# isoDebug-FTDI.net
KiCad netlist of a schematic drawn in Altium Designer
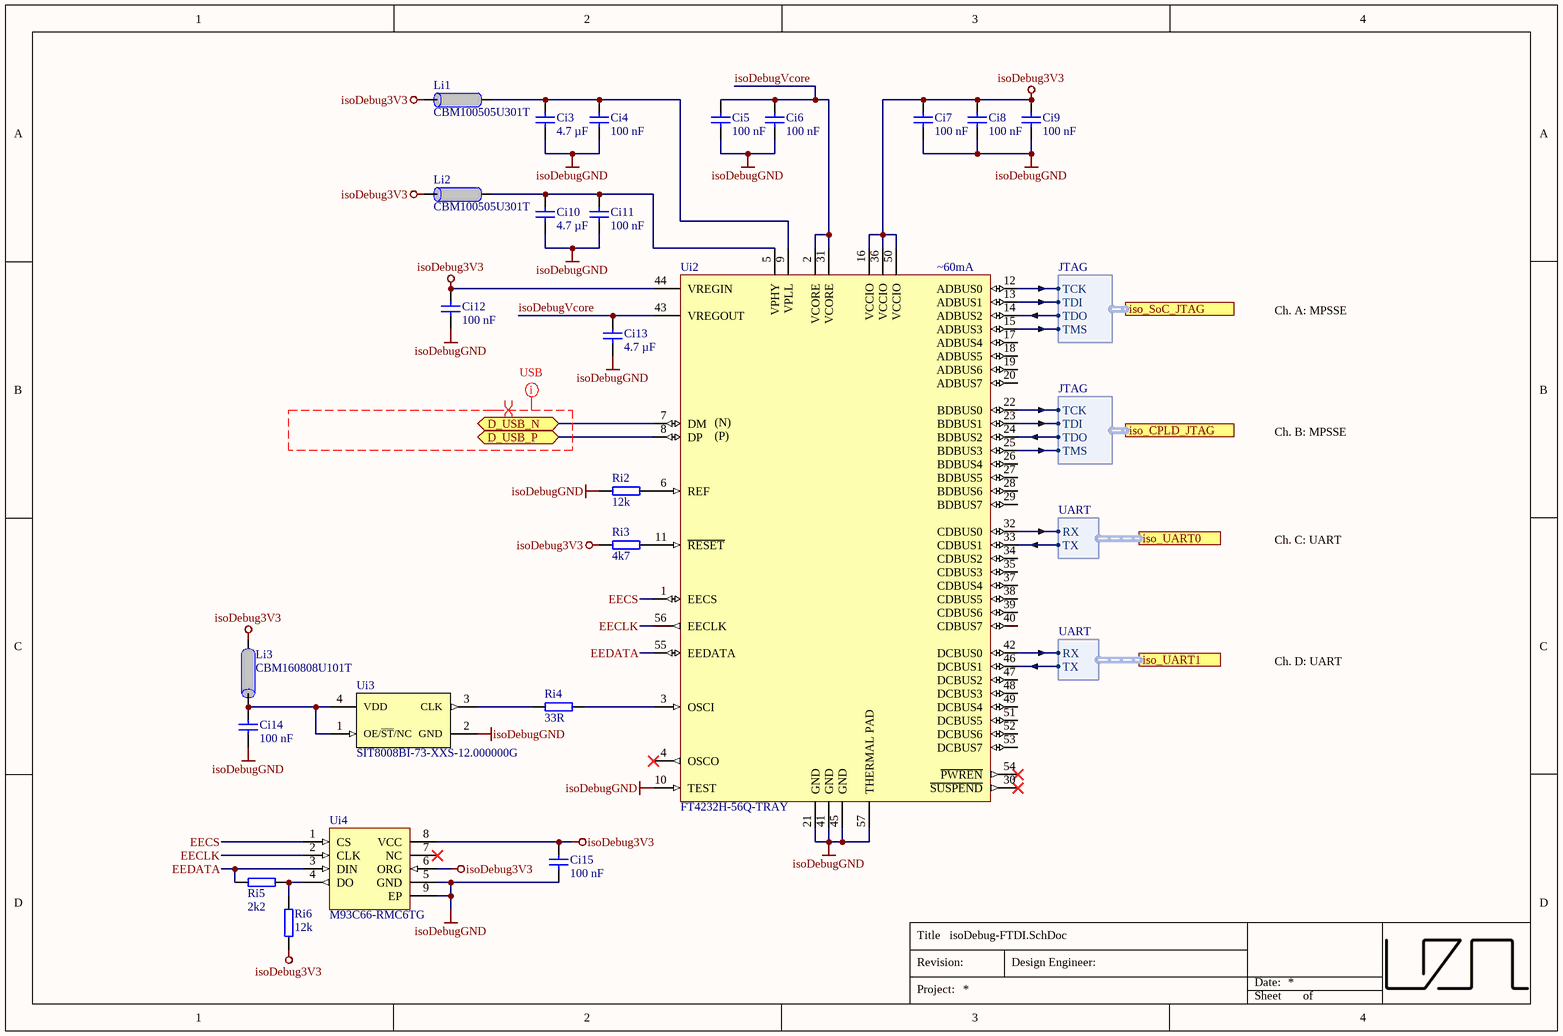
[diagram p0: isoDebug-FTDI.SchDoc]

(export (version "E")
  (design (tool "Eeschema 10.0.6"))
  (components
    (comp (ref "Ci3")
      (value "4.7 µF")
      (footprint "C_0603_TE")
      (description "Generic capacitor")
      (fields
        (field (name "MANUFACTURER PART NUMBER") "UZgen_C_0603_4.7uF_16V_X5R")
        (field (name "MANUFACTURER") "UZgen")
        (field (name "CREATED FROM") "MGeier")
      )
      (libsource (lib "user") (part "CAP-NP"))
    )
    (comp (ref "Ci4")
      (value "100 nF")
      (footprint "C_0402_TE")
      (description "Generic capacitor")
      (fields
        (field (name "MANUFACTURER PART NUMBER") "UZgen_C_0402_100nF_50V_X7R")
        (field (name "MANUFACTURER") "UZgen")
        (field (name "CREATED FROM") "UZgenTool")
      )
      (libsource (lib "user") (part "CAP-NP"))
    )
    (comp (ref "Ci5")
      (value "100 nF")
      (footprint "C_0402_TE")
      (description "Generic capacitor")
      (fields
        (field (name "MANUFACTURER PART NUMBER") "UZgen_C_0402_100nF_50V_X7R")
        (field (name "MANUFACTURER") "UZgen")
        (field (name "CREATED FROM") "UZgenTool")
      )
      (libsource (lib "user") (part "CAP-NP"))
    )
    (comp (ref "Ci6")
      (value "100 nF")
      (footprint "C_0402_TE")
      (description "Generic capacitor")
      (fields
        (field (name "MANUFACTURER PART NUMBER") "UZgen_C_0402_100nF_50V_X7R")
        (field (name "MANUFACTURER") "UZgen")
        (field (name "CREATED FROM") "UZgenTool")
      )
      (libsource (lib "user") (part "CAP-NP"))
    )
    (comp (ref "Ci7")
      (value "100 nF")
      (footprint "C_0402_TE")
      (description "Generic capacitor")
      (fields
        (field (name "MANUFACTURER PART NUMBER") "UZgen_C_0402_100nF_50V_X7R")
        (field (name "MANUFACTURER") "UZgen")
        (field (name "CREATED FROM") "UZgenTool")
      )
      (libsource (lib "user") (part "CAP-NP"))
    )
    (comp (ref "Ci8")
      (value "100 nF")
      (footprint "C_0402_TE")
      (description "Generic capacitor")
      (fields
        (field (name "MANUFACTURER PART NUMBER") "UZgen_C_0402_100nF_50V_X7R")
        (field (name "MANUFACTURER") "UZgen")
        (field (name "CREATED FROM") "UZgenTool")
      )
      (libsource (lib "user") (part "CAP-NP"))
    )
    (comp (ref "Ci9")
      (value "100 nF")
      (footprint "C_0402_TE")
      (description "Generic capacitor")
      (fields
        (field (name "MANUFACTURER PART NUMBER") "UZgen_C_0402_100nF_50V_X7R")
        (field (name "MANUFACTURER") "UZgen")
        (field (name "CREATED FROM") "UZgenTool")
      )
      (libsource (lib "user") (part "CAP-NP"))
    )
    (comp (ref "Ci10")
      (value "4.7 µF")
      (footprint "C_0603_TE")
      (description "Generic capacitor")
      (fields
        (field (name "MANUFACTURER PART NUMBER") "UZgen_C_0603_4.7uF_16V_X5R")
        (field (name "MANUFACTURER") "UZgen")
        (field (name "CREATED FROM") "MGeier")
      )
      (libsource (lib "user") (part "CAP-NP"))
    )
    (comp (ref "Ci11")
      (value "100 nF")
      (footprint "C_0402_TE")
      (description "Generic capacitor")
      (fields
        (field (name "MANUFACTURER PART NUMBER") "UZgen_C_0402_100nF_50V_X7R")
        (field (name "MANUFACTURER") "UZgen")
        (field (name "CREATED FROM") "UZgenTool")
      )
      (libsource (lib "user") (part "CAP-NP"))
    )
    (comp (ref "Ci12")
      (value "100 nF")
      (footprint "C_0402_TE")
      (description "Generic capacitor")
      (fields
        (field (name "MANUFACTURER PART NUMBER") "UZgen_C_0402_100nF_50V_X7R")
        (field (name "MANUFACTURER") "UZgen")
        (field (name "CREATED FROM") "UZgenTool")
      )
      (libsource (lib "user") (part "CAP-NP"))
    )
    (comp (ref "Ci13")
      (value "4.7 µF")
      (footprint "C_0603_TE")
      (description "Generic capacitor")
      (fields
        (field (name "MANUFACTURER PART NUMBER") "UZgen_C_0603_4.7uF_16V_X5R")
        (field (name "MANUFACTURER") "UZgen")
        (field (name "CREATED FROM") "MGeier")
      )
      (libsource (lib "user") (part "CAP-NP"))
    )
    (comp (ref "Ci14")
      (value "100 nF")
      (footprint "C_0402_TE")
      (description "Generic capacitor")
      (fields
        (field (name "MANUFACTURER PART NUMBER") "UZgen_C_0402_100nF_50V_X7R")
        (field (name "MANUFACTURER") "UZgen")
        (field (name "CREATED FROM") "UZgenTool")
      )
      (libsource (lib "user") (part "CAP-NP"))
    )
    (comp (ref "Ci15")
      (value "100 nF")
      (footprint "C_0402_TE")
      (description "Generic capacitor")
      (fields
        (field (name "MANUFACTURER PART NUMBER") "UZgen_C_0402_100nF_50V_X7R")
        (field (name "MANUFACTURER") "UZgen")
        (field (name "CREATED FROM") "UZgenTool")
      )
      (libsource (lib "user") (part "CAP-NP"))
    )
    (comp (ref "Li1")
      (value "CBM100505U301T")
      (footprint "IND_0402_TE")
      (description "300mΩ ±25% 300Ω@100MHz 0402 Ferrite Beads ROHS")
      (fields
        (field (name "MANUFACTURER") "FH (Guangdong Fenghua Advanced Tech)")
        (field (name "LCSC PART NUMBER") "C394406")
        (field (name "CREATED FROM") "AGeiger")
      )
      (libsource (lib "") (part "Ferrite_Bead_1"))
    )
    (comp (ref "Li2")
      (value "CBM100505U301T")
      (footprint "IND_0402_TE")
      (description "300mΩ ±25% 300Ω@100MHz 0402 Ferrite Beads ROHS")
      (fields
        (field (name "MANUFACTURER") "FH (Guangdong Fenghua Advanced Tech)")
        (field (name "LCSC PART NUMBER") "C394406")
        (field (name "CREATED FROM") "AGeiger")
      )
      (libsource (lib "") (part "Ferrite_Bead_1"))
    )
    (comp (ref "Li3")
      (value "CBM160808U101T")
      (footprint "IND_0603_TE")
      (description "60mΩ ±25% 100Ω@100MHz 0603 Ferrite Beads ROHS")
      (fields
        (field (name "MANUFACTURER") "FH (Guangdong Fenghua Advanced Tech)")
        (field (name "LCSC PART NUMBER") "C361675")
        (field (name "CREATED FROM") "AGeiger")
      )
      (libsource (lib "user") (part "Ferrite_Bead"))
    )
    (comp (ref "Ri2")
      (value "12k")
      (footprint "R_0603_TE")
      (description "Generic resistor")
      (fields
        (field (name "MANUFACTURER PART NUMBER") "UZgen_R_0603_12k")
        (field (name "MANUFACTURER") "UZgen")
        (field (name "CREATED FROM") "UZgenTool")
      )
      (libsource (lib "user") (part "RES"))
    )
    (comp (ref "Ri3")
      (value "4k7")
      (footprint "R_0603_TE")
      (description "Generic resistor")
      (fields
        (field (name "MANUFACTURER PART NUMBER") "UZgen_R_0603_4k7")
        (field (name "MANUFACTURER") "UZgen")
        (field (name "CREATED FROM") "UZgenTool")
      )
      (libsource (lib "user") (part "RES"))
    )
    (comp (ref "Ri4")
      (value "33R")
      (footprint "R_0603_TE")
      (description "Generic resistor")
      (fields
        (field (name "MANUFACTURER PART NUMBER") "UZgen_R_0603_33R")
        (field (name "MANUFACTURER") "UZgen")
        (field (name "CREATED FROM") "UZgenTool")
      )
      (libsource (lib "user") (part "RES"))
    )
    (comp (ref "Ri5")
      (value "2k2")
      (footprint "R_0603_TE")
      (description "Generic resistor")
      (fields
        (field (name "MANUFACTURER PART NUMBER") "UZgen_R_0603_2k2")
        (field (name "MANUFACTURER") "UZgen")
        (field (name "CREATED FROM") "UZgenTool")
      )
      (libsource (lib "user") (part "RES"))
    )
    (comp (ref "Ri6")
      (value "12k")
      (footprint "R_0603_TE")
      (description "Generic resistor")
      (fields
        (field (name "MANUFACTURER PART NUMBER") "UZgen_R_0603_12k")
        (field (name "MANUFACTURER") "UZgen")
        (field (name "CREATED FROM") "UZgenTool")
      )
      (libsource (lib "user") (part "RES"))
    )
    (comp (ref "Ui2")
      (value "FT4232H-56Q-TRAY")
      (footprint "QFN50P800X800-57T610X610N")
      (description "USB Interface IC Quad 480Mbs 4 UART USB 2.0 12Mbit")
      (fields
        (field (name "MANUFACTURER") "FTDI")
        (field (name "LCSC PART NUMBER") "C1521561")
        (field (name "CREATED FROM") "AGeiger")
      )
      (libsource (lib "user") (part "FT4232H-56Q"))
    )
    (comp (ref "Ui3")
      (value "SIT8008BI-73-XXS-12.000000G")
      (footprint "2016")
      (description "Clock-Standardoszillatoren -40 to 85C, 2016, 50ppm, 2.25V-3.63V, 12MHz, ST, 250 pcs T&R 8 mm")
      (fields
        (field (name "MANUFACTURER") "SiTime")
        (field (name "LCSC PART NUMBER") "C1508636")
        (field (name "CREATED FROM") "AGeiger")
      )
      (libsource (lib "user") (part "SiT8103"))
    )
    (comp (ref "Ui4")
      (value "M93C66-RMC6TG")
      (footprint "UFDFPN8")
      (description "4Kbit MICROWIRE EE 1.8 V to 5.5 V")
      (fields
        (field (name "MANUFACTURER") "STMicroelectronics")
        (field (name "LCSC PART NUMBER") "C2061956")
        (field (name "CREATED FROM") "AGeiger")
      )
      (libsource (lib "user") (part "M93C46-MN6P"))
    )
  )
  (nets
    (net (code "3") (name "/D_USB_N") (class "Default")
      (node (ref "Ui2") (pin "7") (pinfunction "DM_7") (pintype "bidirectional"))
    )
    (net (code "4") (name "/D_USB_P") (class "Default")
      (node (ref "Ui2") (pin "8") (pinfunction "DP_8") (pintype "bidirectional"))
    )
    (net (code "5") (name "/EECLK") (class "Default")
      (node (ref "Ui2") (pin "56") (pinfunction "EECLK_56") (pintype "output"))
      (node (ref "Ui4") (pin "2") (pinfunction "CLK_2") (pintype "input"))
    )
    (net (code "6") (name "/EECS") (class "Default")
      (node (ref "Ui2") (pin "1") (pinfunction "EECS_1") (pintype "bidirectional"))
      (node (ref "Ui4") (pin "1") (pinfunction "CS_1") (pintype "input"))
    )
    (net (code "7") (name "/EEDATA") (class "Default")
      (node (ref "Ri5") (pin "1") (pinfunction "1_1") (pintype "passive"))
      (node (ref "Ui2") (pin "55") (pinfunction "EEDATA_55") (pintype "bidirectional"))
      (node (ref "Ui4") (pin "3") (pinfunction "DIN_3") (pintype "input"))
    )
    (net (code "8") (name "/isoDebugVcore") (class "Default")
      (node (ref "Ci13") (pin "2") (pinfunction "2_2") (pintype "passive"))
      (node (ref "Ci5") (pin "2") (pinfunction "2_2") (pintype "passive"))
      (node (ref "Ci6") (pin "2") (pinfunction "2_2") (pintype "passive"))
      (node (ref "Ui2") (pin "2") (pinfunction "VCORE_2") (pintype "power_in"))
      (node (ref "Ui2") (pin "31") (pinfunction "VCORE_31") (pintype "power_in"))
      (node (ref "Ui2") (pin "43") (pinfunction "VREGOUT_43") (pintype "power_in"))
    )
    (net (code "11") (name "Net-(Ui2-OSCI)") (class "Default")
      (node (ref "Ri4") (pin "2") (pinfunction "2_2") (pintype "passive"))
      (node (ref "Ui2") (pin "3") (pinfunction "OSCI_3") (pintype "input"))
    )
    (net (code "12") (name "Net-(Ui2-REF)") (class "Default")
      (node (ref "Ri2") (pin "2") (pinfunction "2_2") (pintype "passive"))
      (node (ref "Ui2") (pin "6") (pinfunction "REF_6") (pintype "input"))
    )
    (net (code "13") (name "Net-(Ui2-VPHY)") (class "Default")
      (node (ref "Ci10") (pin "2") (pinfunction "2_2") (pintype "passive"))
      (node (ref "Ci11") (pin "2") (pinfunction "2_2") (pintype "passive"))
      (node (ref "Li2") (pin "1") (pinfunction "1_1") (pintype "passive"))
      (node (ref "Ui2") (pin "5") (pinfunction "VPHY_5") (pintype "power_in"))
    )
    (net (code "14") (name "Net-(Ui2-VPLL)") (class "Default")
      (node (ref "Ci3") (pin "2") (pinfunction "2_2") (pintype "passive"))
      (node (ref "Ci4") (pin "2") (pinfunction "2_2") (pintype "passive"))
      (node (ref "Li1") (pin "1") (pinfunction "1_1") (pintype "passive"))
      (node (ref "Ui2") (pin "9") (pinfunction "VPLL_9") (pintype "power_in"))
    )
    (net (code "15") (name "Net-(Ui2-~{RESET})") (class "Default")
      (node (ref "Ri3") (pin "2") (pinfunction "2_2") (pintype "passive"))
      (node (ref "Ui2") (pin "11") (pinfunction "~{RESET}_11") (pintype "input"))
    )
    (net (code "16") (name "Net-(Ui3-CLK)") (class "Default")
      (node (ref "Ri4") (pin "1") (pinfunction "1_1") (pintype "passive"))
      (node (ref "Ui3") (pin "3") (pinfunction "CLK_3") (pintype "output"))
    )
    (net (code "17") (name "Net-(Ui3-OE{slash}~{ST}{slash}NC)") (class "Default")
      (node (ref "Ci14") (pin "2") (pinfunction "2_2") (pintype "passive"))
      (node (ref "Li3") (pin "2") (pinfunction "2_2") (pintype "passive"))
      (node (ref "Ui3") (pin "1") (pinfunction "OE/~{ST}/NC_1") (pintype "input"))
      (node (ref "Ui3") (pin "4") (pinfunction "VDD_4") (pintype "power_in"))
    )
    (net (code "18") (name "Net-(Ui4-DO)") (class "Default")
      (node (ref "Ri5") (pin "2") (pinfunction "2_2") (pintype "passive"))
      (node (ref "Ri6") (pin "2") (pinfunction "2_2") (pintype "passive"))
      (node (ref "Ui4") (pin "4") (pinfunction "DO_4") (pintype "output"))
    )
    (net (code "19") (name "isoDebug3V3") (class "Default")
      (node (ref "Ci12") (pin "2") (pinfunction "2_2") (pintype "passive"))
      (node (ref "Ci15") (pin "2") (pinfunction "2_2") (pintype "passive"))
      (node (ref "Ci7") (pin "2") (pinfunction "2_2") (pintype "passive"))
      (node (ref "Ci8") (pin "2") (pinfunction "2_2") (pintype "passive"))
      (node (ref "Ci9") (pin "2") (pinfunction "2_2") (pintype "passive"))
      (node (ref "Li1") (pin "2") (pinfunction "2_2") (pintype "passive"))
      (node (ref "Li2") (pin "2") (pinfunction "2_2") (pintype "passive"))
      (node (ref "Li3") (pin "1") (pinfunction "1_1") (pintype "passive"))
      (node (ref "Ri3") (pin "1") (pinfunction "1_1") (pintype "passive"))
      (node (ref "Ri6") (pin "1") (pinfunction "1_1") (pintype "passive"))
      (node (ref "Ui2") (pin "16") (pinfunction "VCCIO_16") (pintype "power_in"))
      (node (ref "Ui2") (pin "36") (pinfunction "VCCIO_36") (pintype "power_in"))
      (node (ref "Ui2") (pin "44") (pinfunction "VREGIN_44") (pintype "power_in"))
      (node (ref "Ui2") (pin "50") (pinfunction "VCCIO_50") (pintype "power_in"))
      (node (ref "Ui4") (pin "6") (pinfunction "ORG_6") (pintype "input"))
      (node (ref "Ui4") (pin "8") (pinfunction "VCC_8") (pintype "power_in"))
    )
    (net (code "20") (name "isoDebugGND") (class "Default")
      (node (ref "Ci10") (pin "1") (pinfunction "1_1") (pintype "passive"))
      (node (ref "Ci11") (pin "1") (pinfunction "1_1") (pintype "passive"))
      (node (ref "Ci12") (pin "1") (pinfunction "1_1") (pintype "passive"))
      (node (ref "Ci13") (pin "1") (pinfunction "1_1") (pintype "passive"))
      (node (ref "Ci14") (pin "1") (pinfunction "1_1") (pintype "passive"))
      (node (ref "Ci15") (pin "1") (pinfunction "1_1") (pintype "passive"))
      (node (ref "Ci3") (pin "1") (pinfunction "1_1") (pintype "passive"))
      (node (ref "Ci4") (pin "1") (pinfunction "1_1") (pintype "passive"))
      (node (ref "Ci5") (pin "1") (pinfunction "1_1") (pintype "passive"))
      (node (ref "Ci6") (pin "1") (pinfunction "1_1") (pintype "passive"))
      (node (ref "Ci7") (pin "1") (pinfunction "1_1") (pintype "passive"))
      (node (ref "Ci8") (pin "1") (pinfunction "1_1") (pintype "passive"))
      (node (ref "Ci9") (pin "1") (pinfunction "1_1") (pintype "passive"))
      (node (ref "Ri2") (pin "1") (pinfunction "1_1") (pintype "passive"))
      (node (ref "Ui2") (pin "10") (pinfunction "TEST_10") (pintype "input"))
      (node (ref "Ui2") (pin "21") (pinfunction "GND_21") (pintype "power_in"))
      (node (ref "Ui2") (pin "41") (pinfunction "GND_41") (pintype "power_in"))
      (node (ref "Ui2") (pin "45") (pinfunction "GND_45") (pintype "power_in"))
      (node (ref "Ui2") (pin "57") (pinfunction "THERMAL_PAD_57") (pintype "power_in"))
      (node (ref "Ui3") (pin "2") (pinfunction "GND_2") (pintype "power_in"))
      (node (ref "Ui4") (pin "5") (pinfunction "GND_5") (pintype "power_in"))
      (node (ref "Ui4") (pin "9") (pinfunction "EP_9") (pintype "power_in"))
    )
    (net (code "21") (name "unconnected-(Ui2-ADBUS0-Pad12)") (class "Default")
      (node (ref "Ui2") (pin "12") (pinfunction "ADBUS0_12") (pintype "bidirectional"))
    )
    (net (code "22") (name "unconnected-(Ui2-ADBUS1-Pad13)") (class "Default")
      (node (ref "Ui2") (pin "13") (pinfunction "ADBUS1_13") (pintype "bidirectional"))
    )
    (net (code "23") (name "unconnected-(Ui2-ADBUS2-Pad14)") (class "Default")
      (node (ref "Ui2") (pin "14") (pinfunction "ADBUS2_14") (pintype "bidirectional"))
    )
    (net (code "24") (name "unconnected-(Ui2-ADBUS3-Pad15)") (class "Default")
      (node (ref "Ui2") (pin "15") (pinfunction "ADBUS3_15") (pintype "bidirectional"))
    )
    (net (code "25") (name "unconnected-(Ui2-ADBUS4-Pad17)") (class "Default")
      (node (ref "Ui2") (pin "17") (pinfunction "ADBUS4_17") (pintype "bidirectional"))
    )
    (net (code "26") (name "unconnected-(Ui2-ADBUS5-Pad18)") (class "Default")
      (node (ref "Ui2") (pin "18") (pinfunction "ADBUS5_18") (pintype "bidirectional"))
    )
    (net (code "27") (name "unconnected-(Ui2-ADBUS6-Pad19)") (class "Default")
      (node (ref "Ui2") (pin "19") (pinfunction "ADBUS6_19") (pintype "bidirectional"))
    )
    (net (code "28") (name "unconnected-(Ui2-ADBUS7-Pad20)") (class "Default")
      (node (ref "Ui2") (pin "20") (pinfunction "ADBUS7_20") (pintype "bidirectional"))
    )
    (net (code "29") (name "unconnected-(Ui2-BDBUS0-Pad22)") (class "Default")
      (node (ref "Ui2") (pin "22") (pinfunction "BDBUS0_22") (pintype "bidirectional"))
    )
    (net (code "30") (name "unconnected-(Ui2-BDBUS1-Pad23)") (class "Default")
      (node (ref "Ui2") (pin "23") (pinfunction "BDBUS1_23") (pintype "bidirectional"))
    )
    (net (code "31") (name "unconnected-(Ui2-BDBUS2-Pad24)") (class "Default")
      (node (ref "Ui2") (pin "24") (pinfunction "BDBUS2_24") (pintype "bidirectional"))
    )
    (net (code "32") (name "unconnected-(Ui2-BDBUS3-Pad25)") (class "Default")
      (node (ref "Ui2") (pin "25") (pinfunction "BDBUS3_25") (pintype "bidirectional"))
    )
    (net (code "33") (name "unconnected-(Ui2-BDBUS4-Pad26)") (class "Default")
      (node (ref "Ui2") (pin "26") (pinfunction "BDBUS4_26") (pintype "bidirectional"))
    )
    (net (code "34") (name "unconnected-(Ui2-BDBUS5-Pad27)") (class "Default")
      (node (ref "Ui2") (pin "27") (pinfunction "BDBUS5_27") (pintype "bidirectional"))
    )
    (net (code "35") (name "unconnected-(Ui2-BDBUS6-Pad28)") (class "Default")
      (node (ref "Ui2") (pin "28") (pinfunction "BDBUS6_28") (pintype "bidirectional"))
    )
    (net (code "36") (name "unconnected-(Ui2-BDBUS7-Pad29)") (class "Default")
      (node (ref "Ui2") (pin "29") (pinfunction "BDBUS7_29") (pintype "bidirectional"))
    )
    (net (code "37") (name "unconnected-(Ui2-CDBUS0-Pad32)") (class "Default")
      (node (ref "Ui2") (pin "32") (pinfunction "CDBUS0_32") (pintype "bidirectional"))
    )
    (net (code "38") (name "unconnected-(Ui2-CDBUS1-Pad33)") (class "Default")
      (node (ref "Ui2") (pin "33") (pinfunction "CDBUS1_33") (pintype "bidirectional"))
    )
    (net (code "39") (name "unconnected-(Ui2-CDBUS2-Pad34)") (class "Default")
      (node (ref "Ui2") (pin "34") (pinfunction "CDBUS2_34") (pintype "bidirectional"))
    )
    (net (code "40") (name "unconnected-(Ui2-CDBUS3-Pad35)") (class "Default")
      (node (ref "Ui2") (pin "35") (pinfunction "CDBUS3_35") (pintype "bidirectional"))
    )
    (net (code "41") (name "unconnected-(Ui2-CDBUS4-Pad37)") (class "Default")
      (node (ref "Ui2") (pin "37") (pinfunction "CDBUS4_37") (pintype "bidirectional"))
    )
    (net (code "42") (name "unconnected-(Ui2-CDBUS5-Pad38)") (class "Default")
      (node (ref "Ui2") (pin "38") (pinfunction "CDBUS5_38") (pintype "bidirectional"))
    )
    (net (code "43") (name "unconnected-(Ui2-CDBUS6-Pad39)") (class "Default")
      (node (ref "Ui2") (pin "39") (pinfunction "CDBUS6_39") (pintype "bidirectional"))
    )
    (net (code "44") (name "unconnected-(Ui2-CDBUS7-Pad40)") (class "Default")
      (node (ref "Ui2") (pin "40") (pinfunction "CDBUS7_40") (pintype "bidirectional"))
    )
    (net (code "45") (name "unconnected-(Ui2-DCBUS0-Pad42)") (class "Default")
      (node (ref "Ui2") (pin "42") (pinfunction "DCBUS0_42") (pintype "bidirectional"))
    )
    (net (code "46") (name "unconnected-(Ui2-DCBUS1-Pad46)") (class "Default")
      (node (ref "Ui2") (pin "46") (pinfunction "DCBUS1_46") (pintype "bidirectional"))
    )
    (net (code "47") (name "unconnected-(Ui2-DCBUS2-Pad47)") (class "Default")
      (node (ref "Ui2") (pin "47") (pinfunction "DCBUS2_47") (pintype "bidirectional"))
    )
    (net (code "48") (name "unconnected-(Ui2-DCBUS3-Pad48)") (class "Default")
      (node (ref "Ui2") (pin "48") (pinfunction "DCBUS3_48") (pintype "bidirectional"))
    )
    (net (code "49") (name "unconnected-(Ui2-DCBUS4-Pad49)") (class "Default")
      (node (ref "Ui2") (pin "49") (pinfunction "DCBUS4_49") (pintype "bidirectional"))
    )
    (net (code "50") (name "unconnected-(Ui2-DCBUS5-Pad51)") (class "Default")
      (node (ref "Ui2") (pin "51") (pinfunction "DCBUS5_51") (pintype "bidirectional"))
    )
    (net (code "51") (name "unconnected-(Ui2-DCBUS6-Pad52)") (class "Default")
      (node (ref "Ui2") (pin "52") (pinfunction "DCBUS6_52") (pintype "bidirectional"))
    )
    (net (code "52") (name "unconnected-(Ui2-DCBUS7-Pad53)") (class "Default")
      (node (ref "Ui2") (pin "53") (pinfunction "DCBUS7_53") (pintype "bidirectional"))
    )
    (net (code "53") (name "unconnected-(Ui2-OSCO-Pad4)") (class "Default")
      (node (ref "Ui2") (pin "4") (pinfunction "OSCO_4") (pintype "output+no_connect"))
    )
    (net (code "54") (name "unconnected-(Ui2-~{PWREN}-Pad54)") (class "Default")
      (node (ref "Ui2") (pin "54") (pinfunction "~{PWREN}_54") (pintype "output+no_connect"))
    )
    (net (code "55") (name "unconnected-(Ui2-~{SUSPEND}-Pad30)") (class "Default")
      (node (ref "Ui2") (pin "30") (pinfunction "~{SUSPEND}_30") (pintype "output+no_connect"))
    )
    (net (code "56") (name "unconnected-(Ui4-NC-Pad7)") (class "Default")
      (node (ref "Ui4") (pin "7") (pinfunction "NC_7") (pintype "passive+no_connect"))
    )
  )
)
